# relayChain5Control.net
KiCad netlist of a schematic drawn in EAGLE
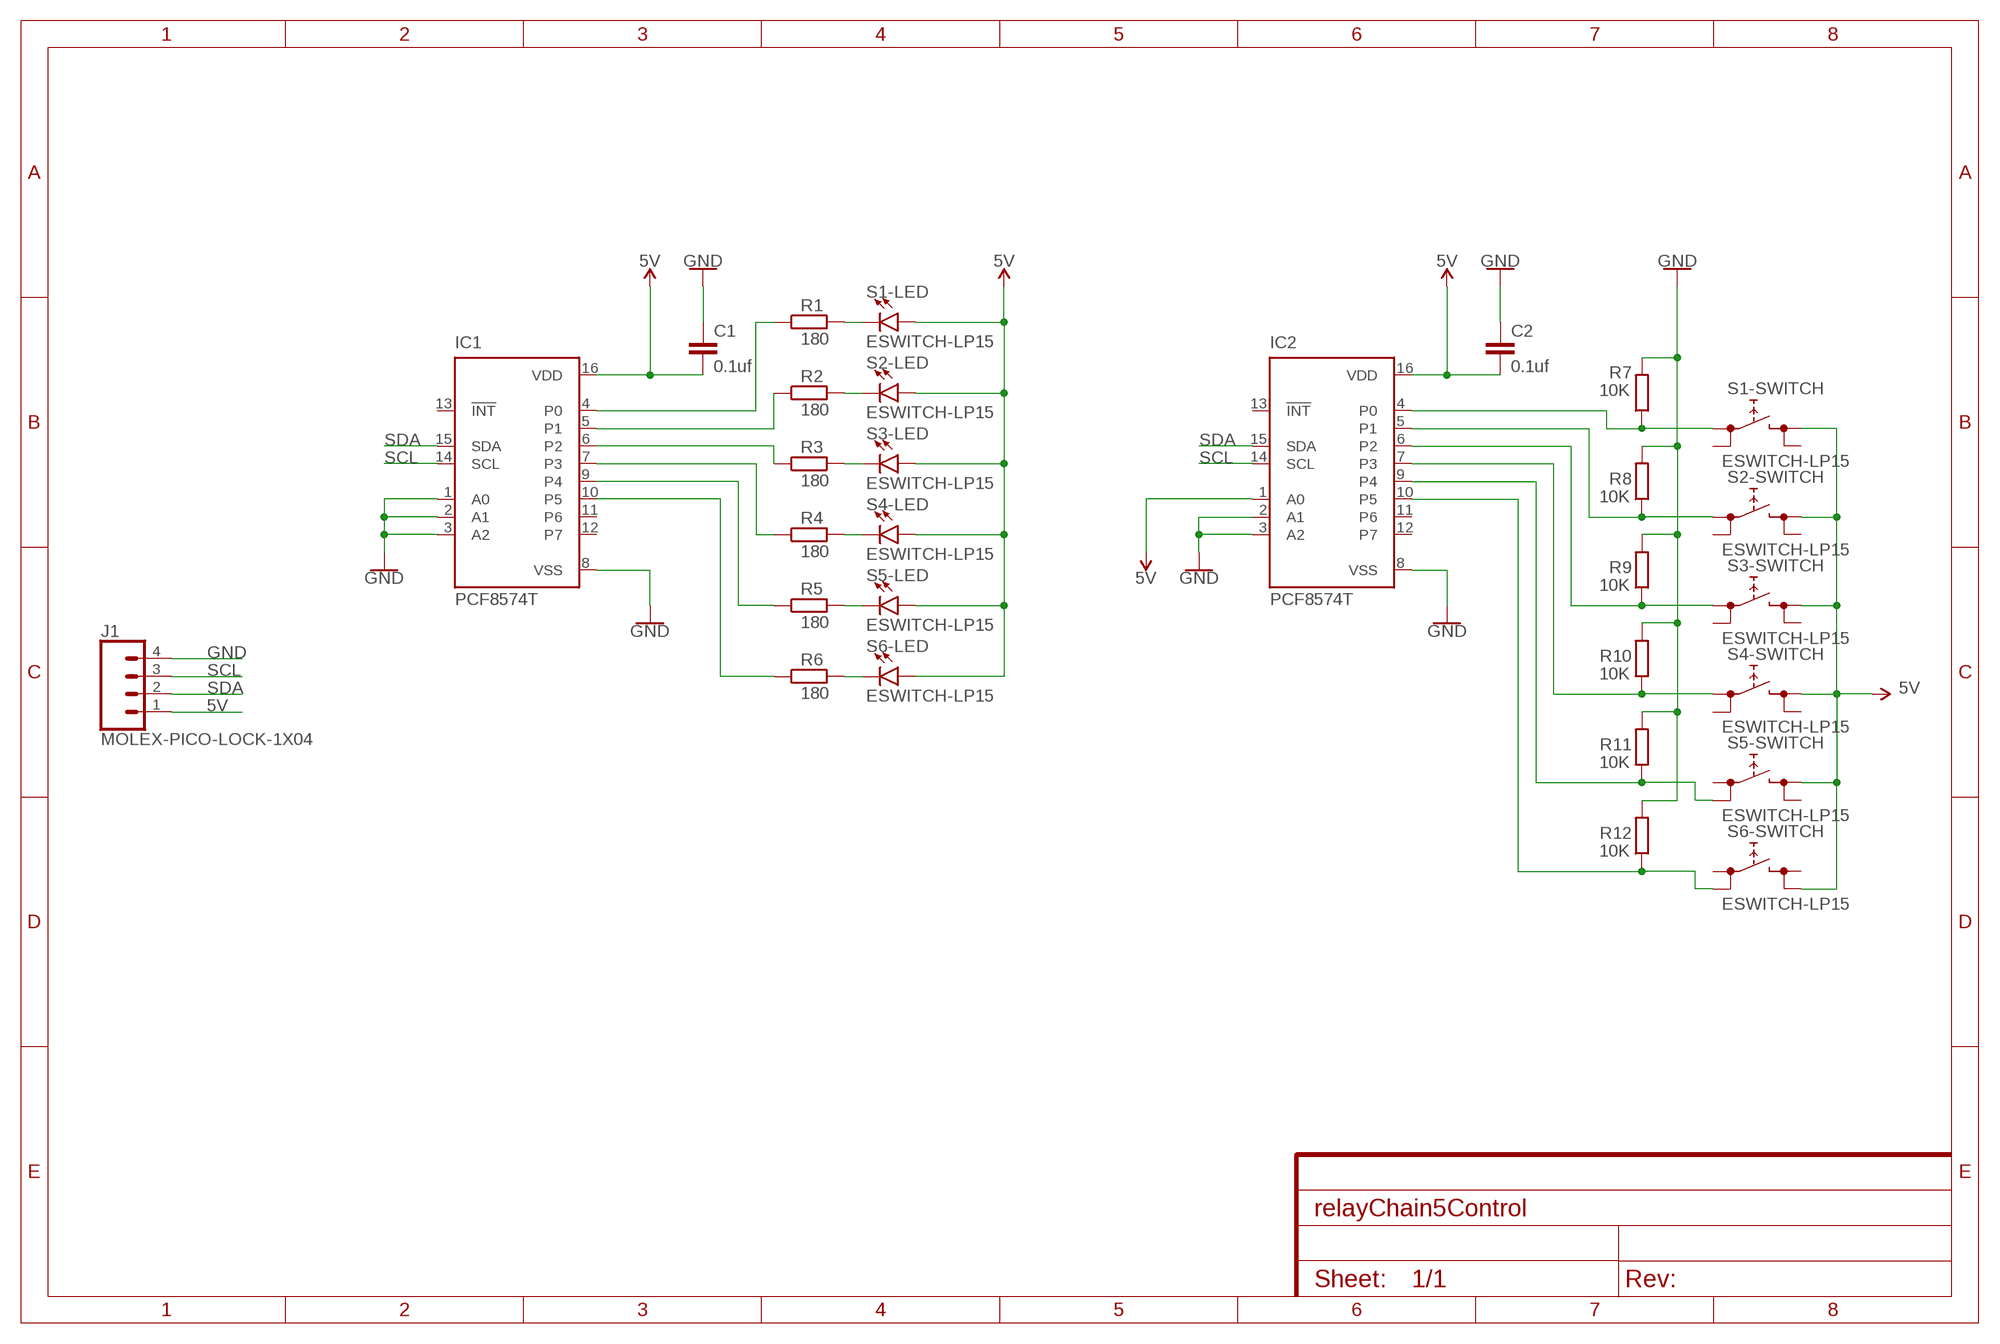
[diagram p0: schematic, sheet 1]

(export (version "E")
  (design (tool "Eeschema 10.0.6"))
  (components
    (comp (ref "C1")
      (value "0.1uf")
      (footprint "eagle-import:C0805")
      (libsource (lib "eagle-import") (part "C-EUC0805"))
    )
    (comp (ref "C2")
      (value "0.1uf")
      (footprint "eagle-import:C0805")
      (libsource (lib "eagle-import") (part "C-EUC0805"))
    )
    (comp (ref "IC1")
      (value "PCF8574T")
      (footprint "eagle-import:SO16W")
      (fields (field (name "MPN") "PCF8574T/3,512"))
      (libsource (lib "eagle-import") (part "PCF8574T"))
    )
    (comp (ref "IC2")
      (value "PCF8574T")
      (footprint "eagle-import:SO16W")
      (fields (field (name "MPN") "PCF8574T/3,512"))
      (libsource (lib "eagle-import") (part "PCF8574T"))
    )
    (comp (ref "J1")
      (value "MOLEX-PICO-LOCK-1X04")
      (footprint "eagle-import:MOLEX-PICO-LOCK-1X04")
      (libsource (lib "eagle-import") (part "MOLEX-PICO-LOCK-1X04"))
    )
    (comp (ref "R1")
      (value "180")
      (footprint "eagle-import:R2012")
      (libsource (lib "eagle-import") (part "R-EU_R2012"))
    )
    (comp (ref "R2")
      (value "180")
      (footprint "eagle-import:R2012")
      (libsource (lib "eagle-import") (part "R-EU_R2012"))
    )
    (comp (ref "R3")
      (value "180")
      (footprint "eagle-import:R2012")
      (libsource (lib "eagle-import") (part "R-EU_R2012"))
    )
    (comp (ref "R4")
      (value "180")
      (footprint "eagle-import:R2012")
      (libsource (lib "eagle-import") (part "R-EU_R2012"))
    )
    (comp (ref "R5")
      (value "180")
      (footprint "eagle-import:R2012")
      (libsource (lib "eagle-import") (part "R-EU_R2012"))
    )
    (comp (ref "R6")
      (value "180")
      (footprint "eagle-import:R2012")
      (libsource (lib "eagle-import") (part "R-EU_R2012"))
    )
    (comp (ref "R7")
      (value "10K")
      (footprint "eagle-import:R2012")
      (libsource (lib "eagle-import") (part "R-EU_R2012"))
    )
    (comp (ref "R8")
      (value "10K")
      (footprint "eagle-import:R2012")
      (libsource (lib "eagle-import") (part "R-EU_R2012"))
    )
    (comp (ref "R9")
      (value "10K")
      (footprint "eagle-import:R2012")
      (libsource (lib "eagle-import") (part "R-EU_R2012"))
    )
    (comp (ref "R10")
      (value "10K")
      (footprint "eagle-import:R2012")
      (libsource (lib "eagle-import") (part "R-EU_R2012"))
    )
    (comp (ref "R11")
      (value "10K")
      (footprint "eagle-import:R2012")
      (libsource (lib "eagle-import") (part "R-EU_R2012"))
    )
    (comp (ref "R12")
      (value "10K")
      (footprint "eagle-import:R2012")
      (libsource (lib "eagle-import") (part "R-EU_R2012"))
    )
    (comp (ref "S1")
      (value "ESWITCH-LP15")
      (footprint "eagle-import:ESWITCH-LP15")
      (libsource (lib "eagle-import") (part "ESWITCH-LP15?"))
    )
    (comp (ref "S2")
      (value "ESWITCH-LP15")
      (footprint "eagle-import:ESWITCH-LP15")
      (libsource (lib "eagle-import") (part "ESWITCH-LP15?"))
    )
    (comp (ref "S3")
      (value "ESWITCH-LP15")
      (footprint "eagle-import:ESWITCH-LP15")
      (libsource (lib "eagle-import") (part "ESWITCH-LP15?"))
    )
    (comp (ref "S4")
      (value "ESWITCH-LP15")
      (footprint "eagle-import:ESWITCH-LP15")
      (libsource (lib "eagle-import") (part "ESWITCH-LP15?"))
    )
    (comp (ref "S5")
      (value "ESWITCH-LP15")
      (footprint "eagle-import:ESWITCH-LP15")
      (libsource (lib "eagle-import") (part "ESWITCH-LP15?"))
    )
    (comp (ref "S6")
      (value "ESWITCH-LP15")
      (footprint "eagle-import:ESWITCH-LP15")
      (libsource (lib "eagle-import") (part "ESWITCH-LP15?"))
    )
  )
  (nets
    (net (code "1") (name "/SCL") (class "Default")
      (node (ref "IC1") (pin "14") (pinfunction "SCL_14") (pintype "input"))
      (node (ref "IC2") (pin "14") (pinfunction "SCL_14") (pintype "input"))
      (node (ref "J1") (pin "3") (pinfunction "3_3") (pintype "passive"))
    )
    (net (code "2") (name "/SDA") (class "Default")
      (node (ref "IC1") (pin "15") (pinfunction "SDA_15") (pintype "bidirectional"))
      (node (ref "IC2") (pin "15") (pinfunction "SDA_15") (pintype "bidirectional"))
      (node (ref "J1") (pin "2") (pinfunction "2_2") (pintype "passive"))
    )
    (net (code "3") (name "5V") (class "Default")
      (node (ref "C1") (pin "2") (pinfunction "2_2") (pintype "passive"))
      (node (ref "C2") (pin "2") (pinfunction "2_2") (pintype "passive"))
      (node (ref "IC1") (pin "16") (pinfunction "VDD_16") (pintype "power_in"))
      (node (ref "IC2") (pin "1") (pinfunction "A0_1") (pintype "input"))
      (node (ref "IC2") (pin "16") (pinfunction "VDD_16") (pintype "power_in"))
      (node (ref "J1") (pin "1") (pinfunction "1_1") (pintype "passive"))
      (node (ref "S1") (pin "P$3") (pinfunction "1_P$3") (pintype "passive"))
      (node (ref "S1") (pin "P$5") (pinfunction "A_P$5") (pintype "passive"))
      (node (ref "S2") (pin "P$3") (pinfunction "1_P$3") (pintype "passive"))
      (node (ref "S2") (pin "P$5") (pinfunction "A_P$5") (pintype "passive"))
      (node (ref "S3") (pin "P$3") (pinfunction "1_P$3") (pintype "passive"))
      (node (ref "S3") (pin "P$5") (pinfunction "A_P$5") (pintype "passive"))
      (node (ref "S4") (pin "P$3") (pinfunction "1_P$3") (pintype "passive"))
      (node (ref "S4") (pin "P$5") (pinfunction "A_P$5") (pintype "passive"))
      (node (ref "S5") (pin "P$3") (pinfunction "1_P$3") (pintype "passive"))
      (node (ref "S5") (pin "P$5") (pinfunction "A_P$5") (pintype "passive"))
      (node (ref "S6") (pin "P$4") (pinfunction "1_P$4") (pintype "passive"))
      (node (ref "S6") (pin "P$5") (pinfunction "A_P$5") (pintype "passive"))
    )
    (net (code "4") (name "GND") (class "Default")
      (node (ref "C1") (pin "1") (pinfunction "1_1") (pintype "passive"))
      (node (ref "C2") (pin "1") (pinfunction "1_1") (pintype "passive"))
      (node (ref "IC1") (pin "1") (pinfunction "A0_1") (pintype "input"))
      (node (ref "IC1") (pin "2") (pinfunction "A1_2") (pintype "input"))
      (node (ref "IC1") (pin "3") (pinfunction "A2_3") (pintype "input"))
      (node (ref "IC1") (pin "8") (pinfunction "VSS_8") (pintype "power_in"))
      (node (ref "IC2") (pin "2") (pinfunction "A1_2") (pintype "input"))
      (node (ref "IC2") (pin "3") (pinfunction "A2_3") (pintype "input"))
      (node (ref "IC2") (pin "8") (pinfunction "VSS_8") (pintype "power_in"))
      (node (ref "J1") (pin "4") (pinfunction "4_4") (pintype "passive"))
      (node (ref "R10") (pin "2") (pinfunction "2_2") (pintype "passive"))
      (node (ref "R11") (pin "2") (pinfunction "2_2") (pintype "passive"))
      (node (ref "R12") (pin "2") (pinfunction "2_2") (pintype "passive"))
      (node (ref "R7") (pin "2") (pinfunction "2_2") (pintype "passive"))
      (node (ref "R8") (pin "2") (pinfunction "2_2") (pintype "passive"))
      (node (ref "R9") (pin "2") (pinfunction "2_2") (pintype "passive"))
    )
    (net (code "5") (name "Net-(IC1-P0)") (class "Default")
      (node (ref "IC1") (pin "4") (pinfunction "P0_4") (pintype "bidirectional"))
      (node (ref "R1") (pin "1") (pinfunction "1_1") (pintype "passive"))
    )
    (net (code "6") (name "Net-(IC1-P1)") (class "Default")
      (node (ref "IC1") (pin "5") (pinfunction "P1_5") (pintype "bidirectional"))
      (node (ref "R2") (pin "1") (pinfunction "1_1") (pintype "passive"))
    )
    (net (code "7") (name "Net-(IC1-P2)") (class "Default")
      (node (ref "IC1") (pin "6") (pinfunction "P2_6") (pintype "bidirectional"))
      (node (ref "R3") (pin "1") (pinfunction "1_1") (pintype "passive"))
    )
    (net (code "8") (name "Net-(IC1-P3)") (class "Default")
      (node (ref "IC1") (pin "7") (pinfunction "P3_7") (pintype "bidirectional"))
      (node (ref "R4") (pin "1") (pinfunction "1_1") (pintype "passive"))
    )
    (net (code "9") (name "Net-(IC1-P4)") (class "Default")
      (node (ref "IC1") (pin "9") (pinfunction "P4_9") (pintype "bidirectional"))
      (node (ref "R5") (pin "1") (pinfunction "1_1") (pintype "passive"))
    )
    (net (code "10") (name "Net-(IC1-P5)") (class "Default")
      (node (ref "IC1") (pin "10") (pinfunction "P5_10") (pintype "bidirectional"))
      (node (ref "R6") (pin "1") (pinfunction "1_1") (pintype "passive"))
    )
    (net (code "11") (name "Net-(IC2-P0)") (class "Default")
      (node (ref "IC2") (pin "4") (pinfunction "P0_4") (pintype "bidirectional"))
      (node (ref "R7") (pin "1") (pinfunction "1_1") (pintype "passive"))
      (node (ref "S1") (pin "P$1") (pinfunction "0_P$1") (pintype "passive"))
    )
    (net (code "12") (name "Net-(IC2-P1)") (class "Default")
      (node (ref "IC2") (pin "5") (pinfunction "P1_5") (pintype "bidirectional"))
      (node (ref "R8") (pin "1") (pinfunction "1_1") (pintype "passive"))
      (node (ref "S2") (pin "P$1") (pinfunction "0_P$1") (pintype "passive"))
    )
    (net (code "13") (name "Net-(IC2-P2)") (class "Default")
      (node (ref "IC2") (pin "6") (pinfunction "P2_6") (pintype "bidirectional"))
      (node (ref "R9") (pin "1") (pinfunction "1_1") (pintype "passive"))
      (node (ref "S3") (pin "P$1") (pinfunction "0_P$1") (pintype "passive"))
    )
    (net (code "14") (name "Net-(IC2-P3)") (class "Default")
      (node (ref "IC2") (pin "7") (pinfunction "P3_7") (pintype "bidirectional"))
      (node (ref "R10") (pin "1") (pinfunction "1_1") (pintype "passive"))
      (node (ref "S4") (pin "P$1") (pinfunction "0_P$1") (pintype "passive"))
    )
    (net (code "15") (name "Net-(IC2-P4)") (class "Default")
      (node (ref "IC2") (pin "9") (pinfunction "P4_9") (pintype "bidirectional"))
      (node (ref "R11") (pin "1") (pinfunction "1_1") (pintype "passive"))
      (node (ref "S5") (pin "P$2") (pinfunction "0_P$2") (pintype "passive"))
    )
    (net (code "16") (name "Net-(IC2-P5)") (class "Default")
      (node (ref "IC2") (pin "10") (pinfunction "P5_10") (pintype "bidirectional"))
      (node (ref "R12") (pin "1") (pinfunction "1_1") (pintype "passive"))
      (node (ref "S6") (pin "P$2") (pinfunction "0_P$2") (pintype "passive"))
    )
    (net (code "17") (name "Net-(S1A-C)") (class "Default")
      (node (ref "R1") (pin "2") (pinfunction "2_2") (pintype "passive"))
      (node (ref "S1") (pin "P$6") (pinfunction "C_P$6") (pintype "passive"))
    )
    (net (code "18") (name "Net-(S2A-C)") (class "Default")
      (node (ref "R2") (pin "2") (pinfunction "2_2") (pintype "passive"))
      (node (ref "S2") (pin "P$6") (pinfunction "C_P$6") (pintype "passive"))
    )
    (net (code "19") (name "Net-(S3A-C)") (class "Default")
      (node (ref "R3") (pin "2") (pinfunction "2_2") (pintype "passive"))
      (node (ref "S3") (pin "P$6") (pinfunction "C_P$6") (pintype "passive"))
    )
    (net (code "20") (name "Net-(S4A-C)") (class "Default")
      (node (ref "R4") (pin "2") (pinfunction "2_2") (pintype "passive"))
      (node (ref "S4") (pin "P$6") (pinfunction "C_P$6") (pintype "passive"))
    )
    (net (code "21") (name "Net-(S5A-C)") (class "Default")
      (node (ref "R5") (pin "2") (pinfunction "2_2") (pintype "passive"))
      (node (ref "S5") (pin "P$6") (pinfunction "C_P$6") (pintype "passive"))
    )
    (net (code "22") (name "Net-(S6A-C)") (class "Default")
      (node (ref "R6") (pin "2") (pinfunction "2_2") (pintype "passive"))
      (node (ref "S6") (pin "P$6") (pinfunction "C_P$6") (pintype "passive"))
    )
    (net (code "23") (name "unconnected-(IC1-P6-Pad11)") (class "Default")
      (node (ref "IC1") (pin "11") (pinfunction "P6_11") (pintype "bidirectional"))
    )
    (net (code "24") (name "unconnected-(IC1-P7-Pad12)") (class "Default")
      (node (ref "IC1") (pin "12") (pinfunction "P7_12") (pintype "bidirectional"))
    )
    (net (code "25") (name "unconnected-(IC1-~{INT}-Pad13)") (class "Default")
      (node (ref "IC1") (pin "13") (pinfunction "~{INT}_13") (pintype "output"))
    )
    (net (code "26") (name "unconnected-(IC2-P6-Pad11)") (class "Default")
      (node (ref "IC2") (pin "11") (pinfunction "P6_11") (pintype "bidirectional"))
    )
    (net (code "27") (name "unconnected-(IC2-P7-Pad12)") (class "Default")
      (node (ref "IC2") (pin "12") (pinfunction "P7_12") (pintype "bidirectional"))
    )
    (net (code "28") (name "unconnected-(IC2-~{INT}-Pad13)") (class "Default")
      (node (ref "IC2") (pin "13") (pinfunction "~{INT}_13") (pintype "output"))
    )
    (net (code "29") (name "unconnected-(S1B-0-PadP$2)") (class "Default")
      (node (ref "S1") (pin "P$2") (pinfunction "0_P$2") (pintype "passive"))
    )
    (net (code "30") (name "unconnected-(S1B-1-PadP$4)") (class "Default")
      (node (ref "S1") (pin "P$4") (pinfunction "1_P$4") (pintype "passive"))
    )
    (net (code "31") (name "unconnected-(S2B-0-PadP$2)") (class "Default")
      (node (ref "S2") (pin "P$2") (pinfunction "0_P$2") (pintype "passive"))
    )
    (net (code "32") (name "unconnected-(S2B-1-PadP$4)") (class "Default")
      (node (ref "S2") (pin "P$4") (pinfunction "1_P$4") (pintype "passive"))
    )
    (net (code "33") (name "unconnected-(S3B-0-PadP$2)") (class "Default")
      (node (ref "S3") (pin "P$2") (pinfunction "0_P$2") (pintype "passive"))
    )
    (net (code "34") (name "unconnected-(S3B-1-PadP$4)") (class "Default")
      (node (ref "S3") (pin "P$4") (pinfunction "1_P$4") (pintype "passive"))
    )
    (net (code "35") (name "unconnected-(S4B-0-PadP$2)") (class "Default")
      (node (ref "S4") (pin "P$2") (pinfunction "0_P$2") (pintype "passive"))
    )
    (net (code "36") (name "unconnected-(S4B-1-PadP$4)") (class "Default")
      (node (ref "S4") (pin "P$4") (pinfunction "1_P$4") (pintype "passive"))
    )
    (net (code "37") (name "unconnected-(S5B-0-PadP$1)") (class "Default")
      (node (ref "S5") (pin "P$1") (pinfunction "0_P$1") (pintype "passive"))
    )
    (net (code "38") (name "unconnected-(S5B-1-PadP$4)") (class "Default")
      (node (ref "S5") (pin "P$4") (pinfunction "1_P$4") (pintype "passive"))
    )
    (net (code "39") (name "unconnected-(S6B-0-PadP$1)") (class "Default")
      (node (ref "S6") (pin "P$1") (pinfunction "0_P$1") (pintype "passive"))
    )
    (net (code "40") (name "unconnected-(S6B-1-PadP$3)") (class "Default")
      (node (ref "S6") (pin "P$3") (pinfunction "1_P$3") (pintype "passive"))
    )
  )
)
